# baremin.net
KiCad netlist of a schematic drawn in EAGLE
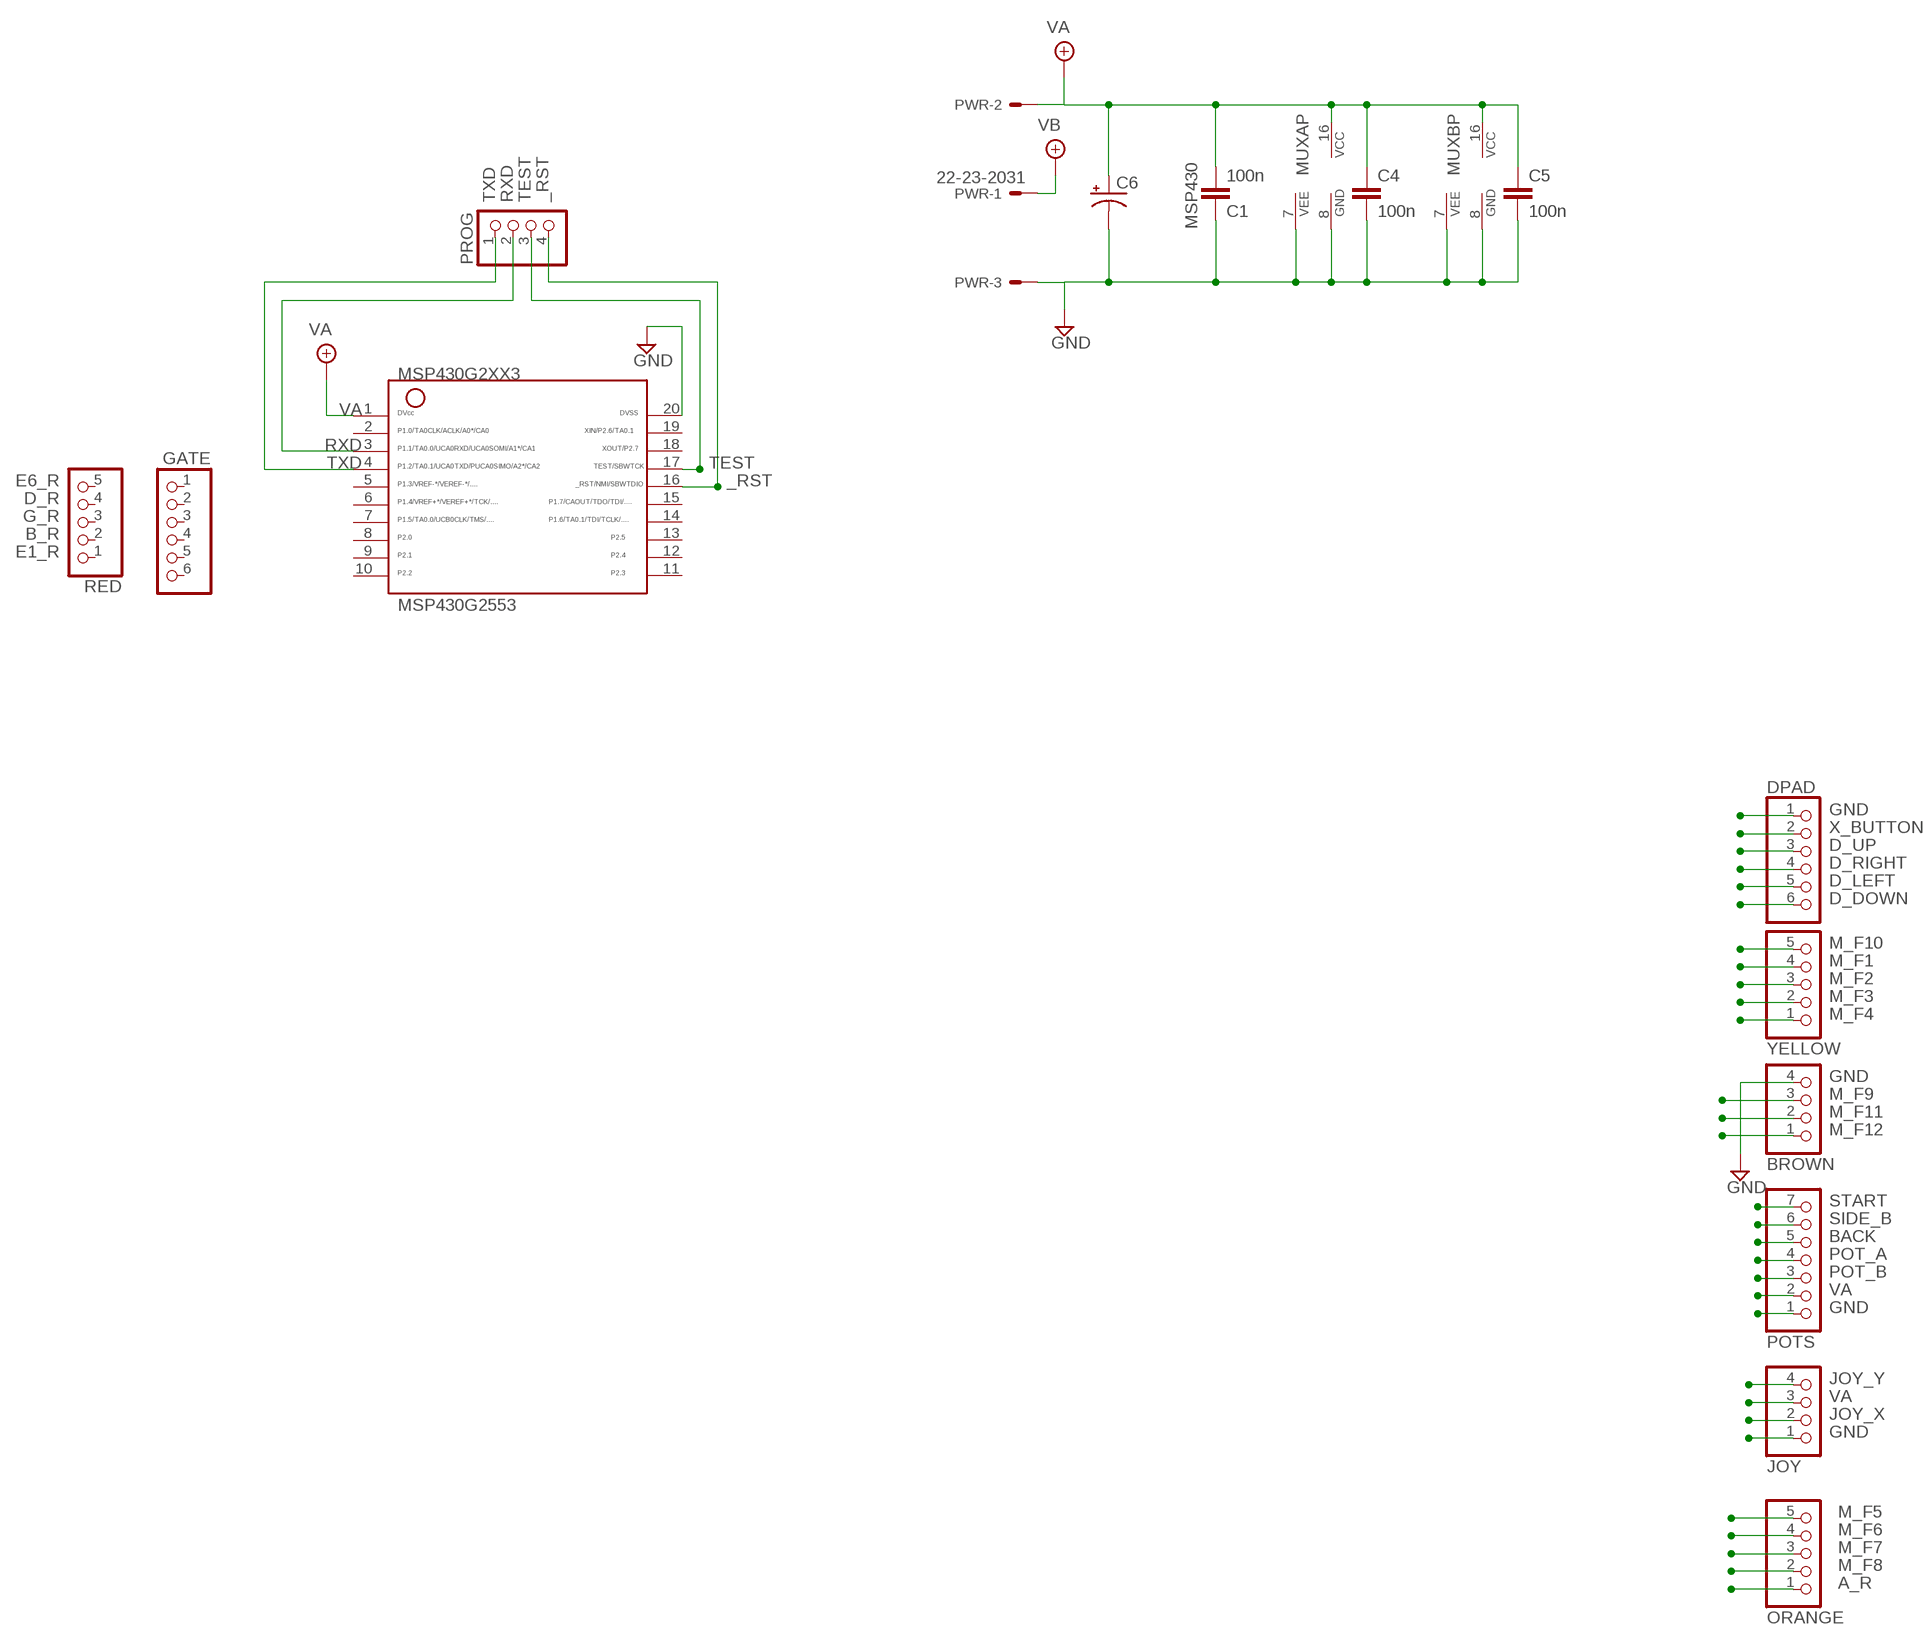
[diagram p0: schematic, sheet 1]

(export (version "E")
  (design (tool "Eeschema 10.0.6"))
  (components
    (comp (ref "BROWN")
      (value "PINHD-1X4")
      (footprint "eagle-import:1X04")
      (libsource (lib "eagle-import") (part "PINHD-1X4"))
    )
    (comp (ref "C1")
      (value "100n")
      (footprint "eagle-import:050X030_050_3")
      (libsource (lib "eagle-import") (part "050X030_050"))
    )
    (comp (ref "C4")
      (value "100n")
      (footprint "eagle-import:050X030_050_1")
      (libsource (lib "eagle-import") (part "050X030_0501"))
    )
    (comp (ref "C5")
      (value "100n")
      (footprint "eagle-import:050X030_050_3")
      (libsource (lib "eagle-import") (part "050X030_050"))
    )
    (comp (ref "C6")
      (value "0501")
      (footprint "eagle-import:050_020_1")
      (libsource (lib "eagle-import") (part "0501"))
    )
    (comp (ref "DPAD")
      (value "PINHD-1X6")
      (footprint "eagle-import:1X06")
      (libsource (lib "eagle-import") (part "PINHD-1X6"))
    )
    (comp (ref "GATE")
      (value "PINHD-1X6")
      (footprint "eagle-import:1X06")
      (libsource (lib "eagle-import") (part "PINHD-1X6"))
    )
    (comp (ref "JOY")
      (value "PINHD-1X4")
      (footprint "eagle-import:1X04")
      (libsource (lib "eagle-import") (part "PINHD-1X4"))
    )
    (comp (ref "MSP430G2553")
      (value "G2XX3---N20")
      (footprint "eagle-import:N20")
      (libsource (lib "eagle-import") (part "G2XX3---N20"))
    )
    (comp (ref "MUXA")
      (value "4051N")
      (footprint "eagle-import:DIL16")
      (libsource (lib "eagle-import") (part "4051N"))
    )
    (comp (ref "MUXB")
      (value "4052N")
      (footprint "eagle-import:DIL16")
      (libsource (lib "eagle-import") (part "4052N"))
    )
    (comp (ref "ORANGE")
      (value "PINHD-1X5")
      (footprint "eagle-import:1X05")
      (libsource (lib "eagle-import") (part "PINHD-1X5"))
    )
    (comp (ref "POTS")
      (value "PINHD-1X7")
      (footprint "eagle-import:1X07")
      (libsource (lib "eagle-import") (part "PINHD-1X7"))
    )
    (comp (ref "PROG")
      (value "PINHD-1X4")
      (footprint "eagle-import:1X04")
      (libsource (lib "eagle-import") (part "PINHD-1X4"))
    )
    (comp (ref "PWR")
      (value "22-23-2031")
      (footprint "eagle-import:22-23-2031")
      (fields (field (name "MF") "MOLEX"))
      (libsource (lib "eagle-import") (part "22-23-2031"))
    )
    (comp (ref "RED")
      (value "PINHD-1X5")
      (footprint "eagle-import:1X05")
      (libsource (lib "eagle-import") (part "PINHD-1X5"))
    )
    (comp (ref "YELLOW")
      (value "PINHD-1X5")
      (footprint "eagle-import:1X05")
      (libsource (lib "eagle-import") (part "PINHD-1X5"))
    )
  )
  (nets
    (net (code "1") (name "/BACK") (class "Default")
      (node (ref "POTS") (pin "7") (pinfunction "7_7") (pintype "passive"))
    )
    (net (code "2") (name "/D_DOWN") (class "Default")
      (node (ref "DPAD") (pin "6") (pinfunction "6_6") (pintype "passive"))
    )
    (net (code "3") (name "/D_LEFT") (class "Default")
      (node (ref "DPAD") (pin "5") (pinfunction "5_5") (pintype "passive"))
    )
    (net (code "4") (name "/D_RIGHT") (class "Default")
      (node (ref "DPAD") (pin "4") (pinfunction "4_4") (pintype "passive"))
    )
    (net (code "5") (name "/D_UP") (class "Default")
      (node (ref "DPAD") (pin "3") (pinfunction "3_3") (pintype "passive"))
    )
    (net (code "6") (name "/JOY_X") (class "Default")
      (node (ref "JOY") (pin "2") (pinfunction "2_2") (pintype "passive"))
    )
    (net (code "7") (name "/JOY_Y") (class "Default")
      (node (ref "JOY") (pin "4") (pinfunction "4_4") (pintype "passive"))
    )
    (net (code "8") (name "/M_F1") (class "Default")
      (node (ref "YELLOW") (pin "4") (pinfunction "4_4") (pintype "passive"))
    )
    (net (code "9") (name "/M_F2") (class "Default")
      (node (ref "YELLOW") (pin "3") (pinfunction "3_3") (pintype "passive"))
    )
    (net (code "10") (name "/M_F3") (class "Default")
      (node (ref "YELLOW") (pin "2") (pinfunction "2_2") (pintype "passive"))
    )
    (net (code "11") (name "/M_F4") (class "Default")
      (node (ref "YELLOW") (pin "1") (pinfunction "1_1") (pintype "passive"))
    )
    (net (code "12") (name "/M_F5") (class "Default")
      (node (ref "ORANGE") (pin "5") (pinfunction "5_5") (pintype "passive"))
    )
    (net (code "13") (name "/M_F6") (class "Default")
      (node (ref "ORANGE") (pin "4") (pinfunction "4_4") (pintype "passive"))
    )
    (net (code "14") (name "/M_F7") (class "Default")
      (node (ref "ORANGE") (pin "3") (pinfunction "3_3") (pintype "passive"))
    )
    (net (code "15") (name "/M_F8") (class "Default")
      (node (ref "ORANGE") (pin "2") (pinfunction "2_2") (pintype "passive"))
    )
    (net (code "16") (name "/M_F9") (class "Default")
      (node (ref "BROWN") (pin "3") (pinfunction "3_3") (pintype "passive"))
    )
    (net (code "17") (name "/M_F10") (class "Default")
      (node (ref "YELLOW") (pin "5") (pinfunction "5_5") (pintype "passive"))
    )
    (net (code "18") (name "/M_F11") (class "Default")
      (node (ref "BROWN") (pin "2") (pinfunction "2_2") (pintype "passive"))
    )
    (net (code "19") (name "/M_F12") (class "Default")
      (node (ref "BROWN") (pin "1") (pinfunction "1_1") (pintype "passive"))
    )
    (net (code "20") (name "/POT_A") (class "Default")
      (node (ref "POTS") (pin "4") (pinfunction "4_4") (pintype "passive"))
    )
    (net (code "21") (name "/POT_B") (class "Default")
      (node (ref "POTS") (pin "3") (pinfunction "3_3") (pintype "passive"))
    )
    (net (code "22") (name "/RXD") (class "Default")
      (node (ref "MSP430G2553") (pin "3") (pinfunction "3_3") (pintype "bidirectional"))
      (node (ref "PROG") (pin "2") (pinfunction "2_2") (pintype "passive"))
    )
    (net (code "23") (name "/SIDE_B") (class "Default")
      (node (ref "POTS") (pin "6") (pinfunction "6_6") (pintype "passive"))
    )
    (net (code "24") (name "/START") (class "Default")
      (node (ref "POTS") (pin "5") (pinfunction "5_5") (pintype "passive"))
    )
    (net (code "25") (name "/TEST") (class "Default")
      (node (ref "MSP430G2553") (pin "17") (pinfunction "17_17") (pintype "bidirectional"))
      (node (ref "PROG") (pin "3") (pinfunction "3_3") (pintype "passive"))
    )
    (net (code "26") (name "/TXD") (class "Default")
      (node (ref "MSP430G2553") (pin "4") (pinfunction "4_4") (pintype "bidirectional"))
      (node (ref "PROG") (pin "1") (pinfunction "1_1") (pintype "passive"))
    )
    (net (code "27") (name "/X_BUTTON") (class "Default")
      (node (ref "DPAD") (pin "2") (pinfunction "2_2") (pintype "passive"))
    )
    (net (code "28") (name "/_RST") (class "Default")
      (node (ref "MSP430G2553") (pin "16") (pinfunction "16_16") (pintype "bidirectional"))
      (node (ref "PROG") (pin "4") (pinfunction "4_4") (pintype "passive"))
    )
    (net (code "29") (name "GND") (class "Default")
      (node (ref "BROWN") (pin "4") (pinfunction "4_4") (pintype "passive"))
      (node (ref "C1") (pin "1") (pinfunction "1_1") (pintype "passive"))
      (node (ref "C4") (pin "2") (pinfunction "2_2") (pintype "passive"))
      (node (ref "C5") (pin "2") (pinfunction "2_2") (pintype "passive"))
      (node (ref "C6") (pin "-") (pinfunction "-_-") (pintype "passive"))
      (node (ref "DPAD") (pin "1") (pinfunction "1_1") (pintype "passive"))
      (node (ref "JOY") (pin "1") (pinfunction "1_1") (pintype "passive"))
      (node (ref "MSP430G2553") (pin "20") (pinfunction "20_20") (pintype "bidirectional"))
      (node (ref "MUXA") (pin "7") (pinfunction "VEE_7") (pintype "power_in"))
      (node (ref "MUXA") (pin "8") (pinfunction "GND_8") (pintype "power_in"))
      (node (ref "MUXB") (pin "7") (pinfunction "VEE_7") (pintype "power_in"))
      (node (ref "MUXB") (pin "8") (pinfunction "GND_8") (pintype "power_in"))
      (node (ref "POTS") (pin "1") (pinfunction "1_1") (pintype "passive"))
      (node (ref "PWR") (pin "3") (pinfunction "S_3") (pintype "passive"))
    )
    (net (code "30") (name "VA") (class "Default")
      (node (ref "C1") (pin "2") (pinfunction "2_2") (pintype "passive"))
      (node (ref "C4") (pin "1") (pinfunction "1_1") (pintype "passive"))
      (node (ref "C5") (pin "1") (pinfunction "1_1") (pintype "passive"))
      (node (ref "C6") (pin "+") (pinfunction "+_+") (pintype "passive"))
      (node (ref "JOY") (pin "3") (pinfunction "3_3") (pintype "passive"))
      (node (ref "MSP430G2553") (pin "1") (pinfunction "1_1") (pintype "bidirectional"))
      (node (ref "MUXA") (pin "16") (pinfunction "VCC_16") (pintype "power_in"))
      (node (ref "MUXB") (pin "16") (pinfunction "VCC_16") (pintype "power_in"))
      (node (ref "POTS") (pin "2") (pinfunction "2_2") (pintype "passive"))
      (node (ref "PWR") (pin "2") (pinfunction "S_2") (pintype "passive"))
    )
    (net (code "31") (name "VB") (class "Default")
      (node (ref "PWR") (pin "1") (pinfunction "S_1") (pintype "passive"))
    )
    (net (code "32") (name "unconnected-(GATE-Pad1)") (class "Default")
      (node (ref "GATE") (pin "1") (pinfunction "1_1") (pintype "passive"))
    )
    (net (code "33") (name "unconnected-(GATE-Pad2)") (class "Default")
      (node (ref "GATE") (pin "2") (pinfunction "2_2") (pintype "passive"))
    )
    (net (code "34") (name "unconnected-(GATE-Pad3)") (class "Default")
      (node (ref "GATE") (pin "3") (pinfunction "3_3") (pintype "passive"))
    )
    (net (code "35") (name "unconnected-(GATE-Pad4)") (class "Default")
      (node (ref "GATE") (pin "4") (pinfunction "4_4") (pintype "passive"))
    )
    (net (code "36") (name "unconnected-(GATE-Pad5)") (class "Default")
      (node (ref "GATE") (pin "5") (pinfunction "5_5") (pintype "passive"))
    )
    (net (code "37") (name "unconnected-(GATE-Pad6)") (class "Default")
      (node (ref "GATE") (pin "6") (pinfunction "6_6") (pintype "passive"))
    )
    (net (code "38") (name "unconnected-(MSP430G2553-Pad2)") (class "Default")
      (node (ref "MSP430G2553") (pin "2") (pinfunction "2_2") (pintype "bidirectional"))
    )
    (net (code "39") (name "unconnected-(MSP430G2553-Pad5)") (class "Default")
      (node (ref "MSP430G2553") (pin "5") (pinfunction "5_5") (pintype "bidirectional"))
    )
    (net (code "40") (name "unconnected-(MSP430G2553-Pad6)") (class "Default")
      (node (ref "MSP430G2553") (pin "6") (pinfunction "6_6") (pintype "bidirectional"))
    )
    (net (code "41") (name "unconnected-(MSP430G2553-Pad7)") (class "Default")
      (node (ref "MSP430G2553") (pin "7") (pinfunction "7_7") (pintype "bidirectional"))
    )
    (net (code "42") (name "unconnected-(MSP430G2553-Pad8)") (class "Default")
      (node (ref "MSP430G2553") (pin "8") (pinfunction "8_8") (pintype "bidirectional"))
    )
    (net (code "43") (name "unconnected-(MSP430G2553-Pad9)") (class "Default")
      (node (ref "MSP430G2553") (pin "9") (pinfunction "9_9") (pintype "bidirectional"))
    )
    (net (code "44") (name "unconnected-(MSP430G2553-Pad10)") (class "Default")
      (node (ref "MSP430G2553") (pin "10") (pinfunction "10_10") (pintype "bidirectional"))
    )
    (net (code "45") (name "unconnected-(MSP430G2553-Pad11)") (class "Default")
      (node (ref "MSP430G2553") (pin "11") (pinfunction "11_11") (pintype "bidirectional"))
    )
    (net (code "46") (name "unconnected-(MSP430G2553-Pad12)") (class "Default")
      (node (ref "MSP430G2553") (pin "12") (pinfunction "12_12") (pintype "bidirectional"))
    )
    (net (code "47") (name "unconnected-(MSP430G2553-Pad13)") (class "Default")
      (node (ref "MSP430G2553") (pin "13") (pinfunction "13_13") (pintype "bidirectional"))
    )
    (net (code "48") (name "unconnected-(MSP430G2553-Pad14)") (class "Default")
      (node (ref "MSP430G2553") (pin "14") (pinfunction "14_14") (pintype "bidirectional"))
    )
    (net (code "49") (name "unconnected-(MSP430G2553-Pad15)") (class "Default")
      (node (ref "MSP430G2553") (pin "15") (pinfunction "15_15") (pintype "bidirectional"))
    )
    (net (code "50") (name "unconnected-(MSP430G2553-Pad18)") (class "Default")
      (node (ref "MSP430G2553") (pin "18") (pinfunction "18_18") (pintype "bidirectional"))
    )
    (net (code "51") (name "unconnected-(MSP430G2553-Pad19)") (class "Default")
      (node (ref "MSP430G2553") (pin "19") (pinfunction "19_19") (pintype "bidirectional"))
    )
    (net (code "52") (name "unconnected-(ORANGE-Pad1)") (class "Default")
      (node (ref "ORANGE") (pin "1") (pinfunction "1_1") (pintype "passive"))
    )
    (net (code "53") (name "unconnected-(RED-Pad1)") (class "Default")
      (node (ref "RED") (pin "1") (pinfunction "1_1") (pintype "passive"))
    )
    (net (code "54") (name "unconnected-(RED-Pad2)") (class "Default")
      (node (ref "RED") (pin "2") (pinfunction "2_2") (pintype "passive"))
    )
    (net (code "55") (name "unconnected-(RED-Pad3)") (class "Default")
      (node (ref "RED") (pin "3") (pinfunction "3_3") (pintype "passive"))
    )
    (net (code "56") (name "unconnected-(RED-Pad4)") (class "Default")
      (node (ref "RED") (pin "4") (pinfunction "4_4") (pintype "passive"))
    )
    (net (code "57") (name "unconnected-(RED-Pad5)") (class "Default")
      (node (ref "RED") (pin "5") (pinfunction "5_5") (pintype "passive"))
    )
  )
)
